# ThroughHoleModule-compact.net
KiCad netlist of a schematic drawn in EAGLE
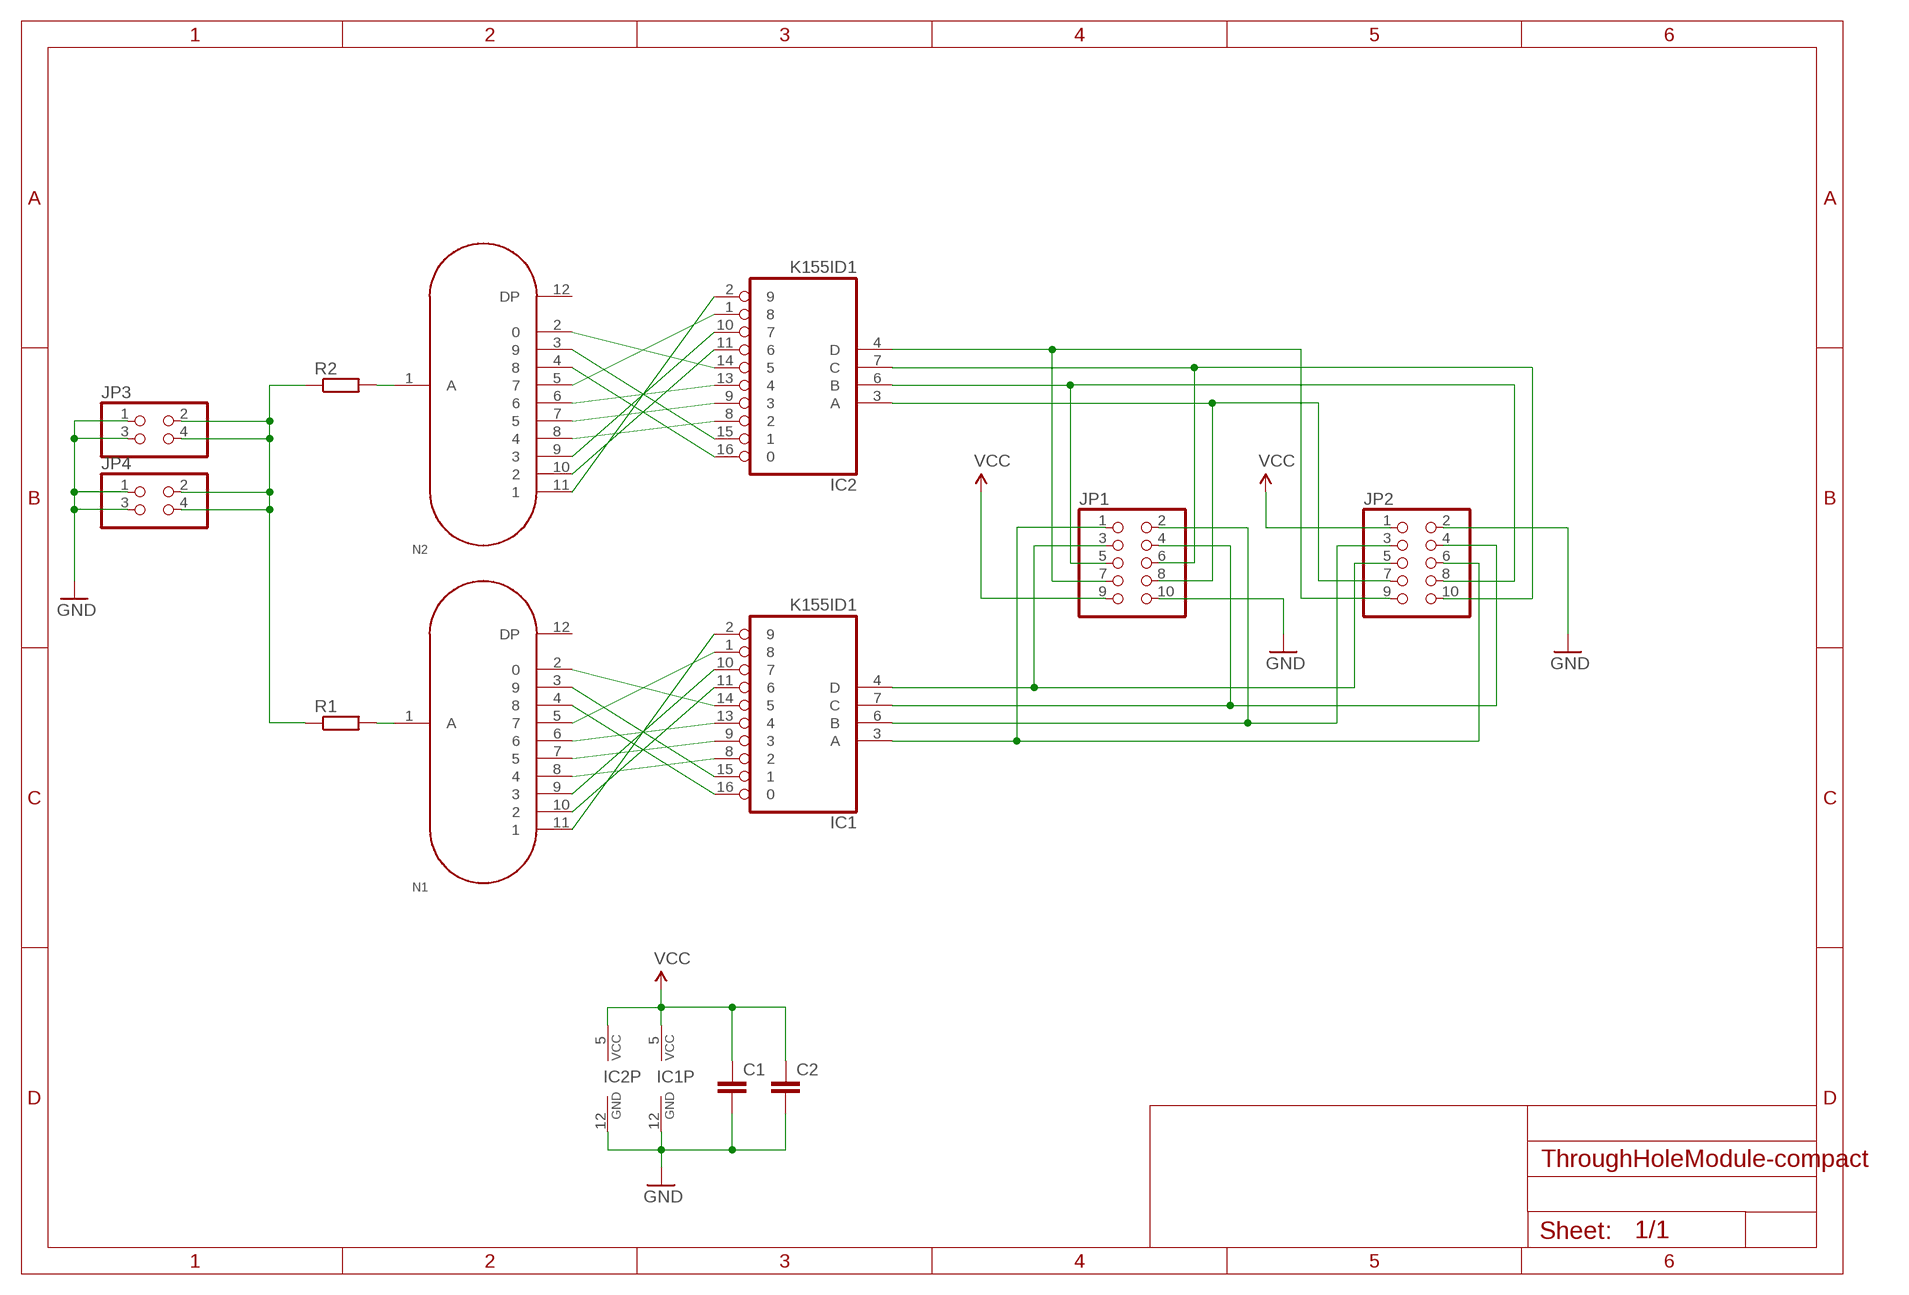
[diagram p0: schematic, sheet 1]

(export (version "E")
  (design (tool "Eeschema 10.0.6"))
  (components
    (comp (ref "C1")
      (value "C-EU050-030X075")
      (footprint "eagle-import:C050-030X075")
      (libsource (lib "eagle-import") (part "C-EU050-030X075"))
    )
    (comp (ref "C2")
      (value "C-EU050-030X075")
      (footprint "eagle-import:C050-030X075")
      (libsource (lib "eagle-import") (part "C-EU050-030X075"))
    )
    (comp (ref "IC1")
      (value "K155ID1")
      (footprint "eagle-import:DIL16")
      (libsource (lib "eagle-import") (part "74141N"))
    )
    (comp (ref "IC2")
      (value "K155ID1")
      (footprint "eagle-import:DIL16")
      (libsource (lib "eagle-import") (part "74141N"))
    )
    (comp (ref "JP1")
      (value "PINHD-2X5")
      (footprint "eagle-import:2X05")
      (libsource (lib "eagle-import") (part "PINHD-2X5"))
    )
    (comp (ref "JP2")
      (value "PINHD-2X5")
      (footprint "eagle-import:2X05")
      (libsource (lib "eagle-import") (part "PINHD-2X5"))
    )
    (comp (ref "JP3")
      (value "PINHD-2X2")
      (footprint "eagle-import:2X02")
      (libsource (lib "eagle-import") (part "PINHD-2X2"))
    )
    (comp (ref "JP4")
      (value "PINHD-2X2")
      (footprint "eagle-import:2X02")
      (libsource (lib "eagle-import") (part "PINHD-2X2"))
    )
    (comp (ref "N1")
      (value "IN-12B")
      (footprint "eagle-import:IN-12")
      (libsource (lib "eagle-import") (part "IN-12B"))
    )
    (comp (ref "N2")
      (value "IN-12B")
      (footprint "eagle-import:IN-12")
      (libsource (lib "eagle-import") (part "IN-12B"))
    )
    (comp (ref "R1")
      (value "R-EU_0207/10")
      (footprint "eagle-import:0207_10")
      (libsource (lib "eagle-import") (part "R-EU_0207/10"))
    )
    (comp (ref "R2")
      (value "R-EU_0207/10")
      (footprint "eagle-import:0207_10")
      (libsource (lib "eagle-import") (part "R-EU_0207/10"))
    )
  )
  (nets
    (net (code "1") (name "GND") (class "Default")
      (node (ref "C1") (pin "2") (pinfunction "2_2") (pintype "passive"))
      (node (ref "C2") (pin "2") (pinfunction "2_2") (pintype "passive"))
      (node (ref "IC1") (pin "12") (pinfunction "GND_12") (pintype "power_in"))
      (node (ref "IC2") (pin "12") (pinfunction "GND_12") (pintype "power_in"))
      (node (ref "JP1") (pin "10") (pinfunction "10_10") (pintype "passive"))
      (node (ref "JP2") (pin "2") (pinfunction "2_2") (pintype "passive"))
      (node (ref "JP3") (pin "1") (pinfunction "1_1") (pintype "passive"))
      (node (ref "JP3") (pin "3") (pinfunction "3_3") (pintype "passive"))
      (node (ref "JP4") (pin "1") (pinfunction "1_1") (pintype "passive"))
      (node (ref "JP4") (pin "3") (pinfunction "3_3") (pintype "passive"))
    )
    (net (code "2") (name "Net-(IC1A-0)") (class "Default")
      (node (ref "IC1") (pin "16") (pinfunction "0_16") (pintype "open_collector"))
      (node (ref "N1") (pin "4") (pinfunction "8_4") (pintype "bidirectional"))
    )
    (net (code "3") (name "Net-(IC1A-1)") (class "Default")
      (node (ref "IC1") (pin "15") (pinfunction "1_15") (pintype "open_collector"))
      (node (ref "N1") (pin "3") (pinfunction "9_3") (pintype "bidirectional"))
    )
    (net (code "4") (name "Net-(IC1A-2)") (class "Default")
      (node (ref "IC1") (pin "8") (pinfunction "2_8") (pintype "open_collector"))
      (node (ref "N1") (pin "8") (pinfunction "4_8") (pintype "bidirectional"))
    )
    (net (code "5") (name "Net-(IC1A-3)") (class "Default")
      (node (ref "IC1") (pin "9") (pinfunction "3_9") (pintype "open_collector"))
      (node (ref "N1") (pin "7") (pinfunction "5_7") (pintype "bidirectional"))
    )
    (net (code "6") (name "Net-(IC1A-4)") (class "Default")
      (node (ref "IC1") (pin "13") (pinfunction "4_13") (pintype "open_collector"))
      (node (ref "N1") (pin "6") (pinfunction "6_6") (pintype "bidirectional"))
    )
    (net (code "7") (name "Net-(IC1A-5)") (class "Default")
      (node (ref "IC1") (pin "14") (pinfunction "5_14") (pintype "open_collector"))
      (node (ref "N1") (pin "2") (pinfunction "0_2") (pintype "bidirectional"))
    )
    (net (code "8") (name "Net-(IC1A-6)") (class "Default")
      (node (ref "IC1") (pin "11") (pinfunction "6_11") (pintype "open_collector"))
      (node (ref "N1") (pin "10") (pinfunction "2_10") (pintype "bidirectional"))
    )
    (net (code "9") (name "Net-(IC1A-7)") (class "Default")
      (node (ref "IC1") (pin "10") (pinfunction "7_10") (pintype "open_collector"))
      (node (ref "N1") (pin "9") (pinfunction "3_9") (pintype "bidirectional"))
    )
    (net (code "10") (name "Net-(IC1A-8)") (class "Default")
      (node (ref "IC1") (pin "1") (pinfunction "8_1") (pintype "open_collector"))
      (node (ref "N1") (pin "5") (pinfunction "7_5") (pintype "bidirectional"))
    )
    (net (code "11") (name "Net-(IC1A-9)") (class "Default")
      (node (ref "IC1") (pin "2") (pinfunction "9_2") (pintype "open_collector"))
      (node (ref "N1") (pin "11") (pinfunction "1_11") (pintype "bidirectional"))
    )
    (net (code "12") (name "Net-(IC1A-A)") (class "Default")
      (node (ref "IC1") (pin "3") (pinfunction "A_3") (pintype "input"))
      (node (ref "JP1") (pin "1") (pinfunction "1_1") (pintype "passive"))
      (node (ref "JP2") (pin "6") (pinfunction "6_6") (pintype "passive"))
    )
    (net (code "13") (name "Net-(IC1A-B)") (class "Default")
      (node (ref "IC1") (pin "6") (pinfunction "B_6") (pintype "input"))
      (node (ref "JP1") (pin "2") (pinfunction "2_2") (pintype "passive"))
      (node (ref "JP2") (pin "3") (pinfunction "3_3") (pintype "passive"))
    )
    (net (code "14") (name "Net-(IC1A-C)") (class "Default")
      (node (ref "IC1") (pin "7") (pinfunction "C_7") (pintype "input"))
      (node (ref "JP1") (pin "4") (pinfunction "4_4") (pintype "passive"))
      (node (ref "JP2") (pin "4") (pinfunction "4_4") (pintype "passive"))
    )
    (net (code "15") (name "Net-(IC1A-D)") (class "Default")
      (node (ref "IC1") (pin "4") (pinfunction "D_4") (pintype "input"))
      (node (ref "JP1") (pin "3") (pinfunction "3_3") (pintype "passive"))
      (node (ref "JP2") (pin "5") (pinfunction "5_5") (pintype "passive"))
    )
    (net (code "16") (name "Net-(IC2A-0)") (class "Default")
      (node (ref "IC2") (pin "16") (pinfunction "0_16") (pintype "open_collector"))
      (node (ref "N2") (pin "4") (pinfunction "8_4") (pintype "bidirectional"))
    )
    (net (code "17") (name "Net-(IC2A-1)") (class "Default")
      (node (ref "IC2") (pin "15") (pinfunction "1_15") (pintype "open_collector"))
      (node (ref "N2") (pin "3") (pinfunction "9_3") (pintype "bidirectional"))
    )
    (net (code "18") (name "Net-(IC2A-2)") (class "Default")
      (node (ref "IC2") (pin "8") (pinfunction "2_8") (pintype "open_collector"))
      (node (ref "N2") (pin "8") (pinfunction "4_8") (pintype "bidirectional"))
    )
    (net (code "19") (name "Net-(IC2A-3)") (class "Default")
      (node (ref "IC2") (pin "9") (pinfunction "3_9") (pintype "open_collector"))
      (node (ref "N2") (pin "7") (pinfunction "5_7") (pintype "bidirectional"))
    )
    (net (code "20") (name "Net-(IC2A-4)") (class "Default")
      (node (ref "IC2") (pin "13") (pinfunction "4_13") (pintype "open_collector"))
      (node (ref "N2") (pin "6") (pinfunction "6_6") (pintype "bidirectional"))
    )
    (net (code "21") (name "Net-(IC2A-5)") (class "Default")
      (node (ref "IC2") (pin "14") (pinfunction "5_14") (pintype "open_collector"))
      (node (ref "N2") (pin "2") (pinfunction "0_2") (pintype "bidirectional"))
    )
    (net (code "22") (name "Net-(IC2A-6)") (class "Default")
      (node (ref "IC2") (pin "11") (pinfunction "6_11") (pintype "open_collector"))
      (node (ref "N2") (pin "10") (pinfunction "2_10") (pintype "bidirectional"))
    )
    (net (code "23") (name "Net-(IC2A-7)") (class "Default")
      (node (ref "IC2") (pin "10") (pinfunction "7_10") (pintype "open_collector"))
      (node (ref "N2") (pin "9") (pinfunction "3_9") (pintype "bidirectional"))
    )
    (net (code "24") (name "Net-(IC2A-8)") (class "Default")
      (node (ref "IC2") (pin "1") (pinfunction "8_1") (pintype "open_collector"))
      (node (ref "N2") (pin "5") (pinfunction "7_5") (pintype "bidirectional"))
    )
    (net (code "25") (name "Net-(IC2A-9)") (class "Default")
      (node (ref "IC2") (pin "2") (pinfunction "9_2") (pintype "open_collector"))
      (node (ref "N2") (pin "11") (pinfunction "1_11") (pintype "bidirectional"))
    )
    (net (code "26") (name "Net-(IC2A-A)") (class "Default")
      (node (ref "IC2") (pin "3") (pinfunction "A_3") (pintype "input"))
      (node (ref "JP1") (pin "8") (pinfunction "8_8") (pintype "passive"))
      (node (ref "JP2") (pin "7") (pinfunction "7_7") (pintype "passive"))
    )
    (net (code "27") (name "Net-(IC2A-B)") (class "Default")
      (node (ref "IC2") (pin "6") (pinfunction "B_6") (pintype "input"))
      (node (ref "JP1") (pin "5") (pinfunction "5_5") (pintype "passive"))
      (node (ref "JP2") (pin "8") (pinfunction "8_8") (pintype "passive"))
    )
    (net (code "28") (name "Net-(IC2A-C)") (class "Default")
      (node (ref "IC2") (pin "7") (pinfunction "C_7") (pintype "input"))
      (node (ref "JP1") (pin "6") (pinfunction "6_6") (pintype "passive"))
      (node (ref "JP2") (pin "10") (pinfunction "10_10") (pintype "passive"))
    )
    (net (code "29") (name "Net-(IC2A-D)") (class "Default")
      (node (ref "IC2") (pin "4") (pinfunction "D_4") (pintype "input"))
      (node (ref "JP1") (pin "7") (pinfunction "7_7") (pintype "passive"))
      (node (ref "JP2") (pin "9") (pinfunction "9_9") (pintype "passive"))
    )
    (net (code "30") (name "Net-(JP3-Pad2)") (class "Default")
      (node (ref "JP3") (pin "2") (pinfunction "2_2") (pintype "passive"))
      (node (ref "JP3") (pin "4") (pinfunction "4_4") (pintype "passive"))
      (node (ref "JP4") (pin "2") (pinfunction "2_2") (pintype "passive"))
      (node (ref "JP4") (pin "4") (pinfunction "4_4") (pintype "passive"))
      (node (ref "R1") (pin "1") (pinfunction "1_1") (pintype "passive"))
      (node (ref "R2") (pin "1") (pinfunction "1_1") (pintype "passive"))
    )
    (net (code "31") (name "Net-(N1-A)") (class "Default")
      (node (ref "N1") (pin "1") (pinfunction "A_1") (pintype "bidirectional"))
      (node (ref "R1") (pin "2") (pinfunction "2_2") (pintype "passive"))
    )
    (net (code "32") (name "Net-(N2-A)") (class "Default")
      (node (ref "N2") (pin "1") (pinfunction "A_1") (pintype "bidirectional"))
      (node (ref "R2") (pin "2") (pinfunction "2_2") (pintype "passive"))
    )
    (net (code "33") (name "VCC") (class "Default")
      (node (ref "C1") (pin "1") (pinfunction "1_1") (pintype "passive"))
      (node (ref "C2") (pin "1") (pinfunction "1_1") (pintype "passive"))
      (node (ref "IC1") (pin "5") (pinfunction "VCC_5") (pintype "power_in"))
      (node (ref "IC2") (pin "5") (pinfunction "VCC_5") (pintype "power_in"))
      (node (ref "JP1") (pin "9") (pinfunction "9_9") (pintype "passive"))
      (node (ref "JP2") (pin "1") (pinfunction "1_1") (pintype "passive"))
    )
    (net (code "34") (name "unconnected-(N1-DP-Pad12)") (class "Default")
      (node (ref "N1") (pin "12") (pinfunction "DP_12") (pintype "bidirectional"))
    )
    (net (code "35") (name "unconnected-(N2-DP-Pad12)") (class "Default")
      (node (ref "N2") (pin "12") (pinfunction "DP_12") (pintype "bidirectional"))
    )
  )
)
